# accBoard.net
KiCad netlist of a schematic drawn in EAGLE
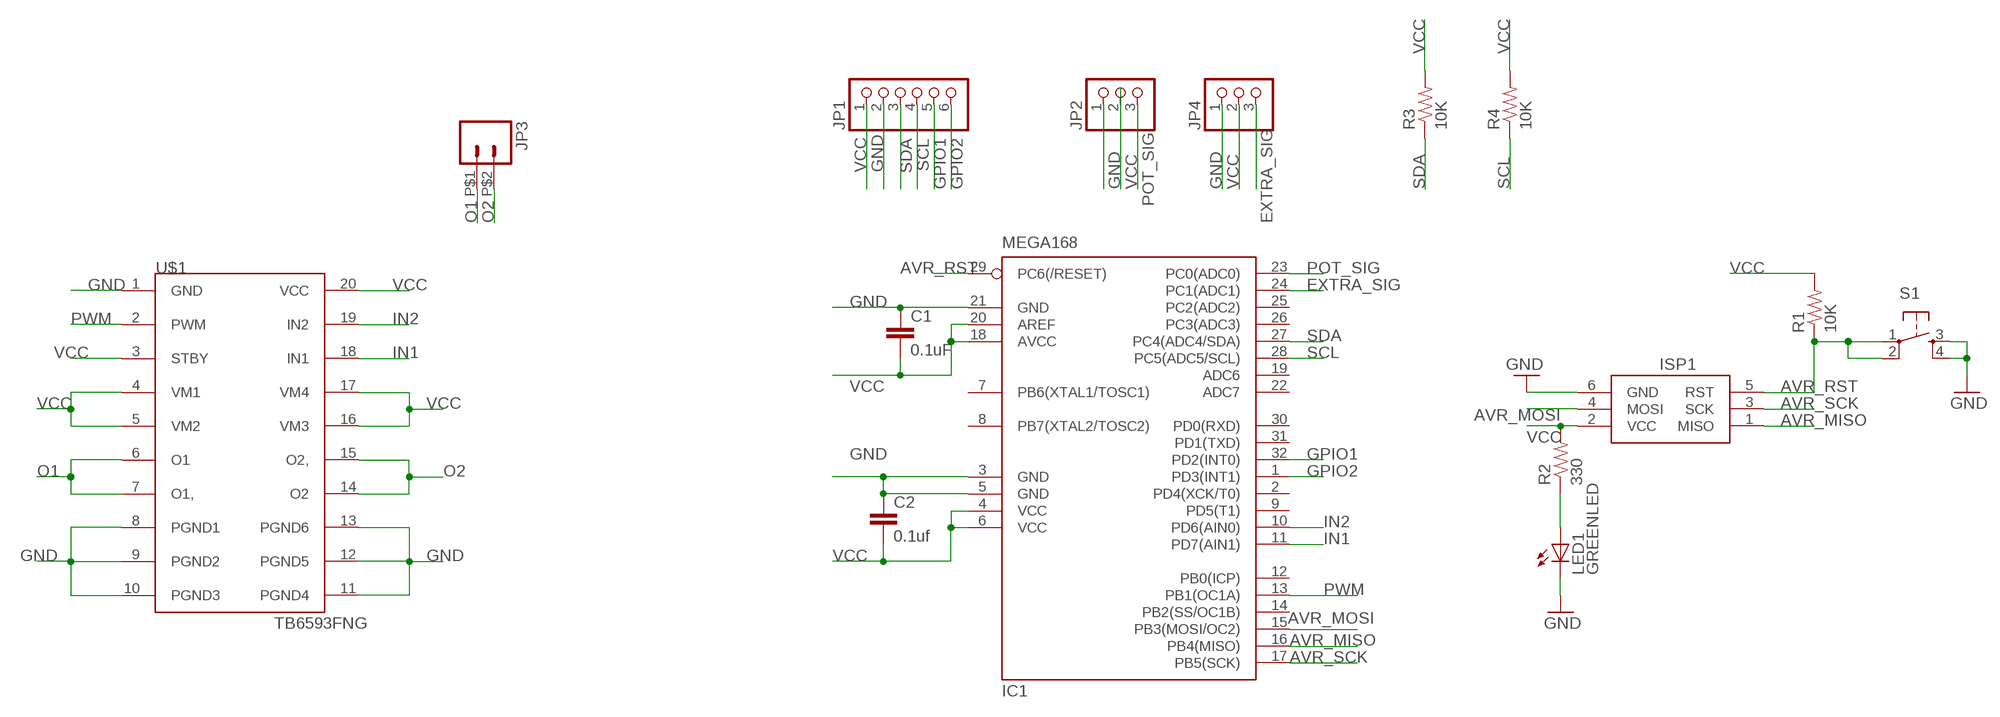
[diagram p0: schematic, sheet 1]

(export (version "E")
  (design (tool "Eeschema 10.0.6"))
  (components
    (comp (ref "C1")
      (value "0.1uF")
      (footprint "eagle-import:0603-CAP")
      (libsource (lib "eagle-import") (part "CAP0603-CAP"))
    )
    (comp (ref "C2")
      (value "0.1uf")
      (footprint "eagle-import:0603-CAP")
      (libsource (lib "eagle-import") (part "CAP0603-CAP"))
    )
    (comp (ref "IC1")
      (value "MEGA168")
      (footprint "eagle-import:TQFP32-08")
      (fields (field (name "MPN") "ATMEGA8-16AU"))
      (libsource (lib "eagle-import") (part "MEGA8-AI"))
    )
    (comp (ref "ISP1")
      (value "AVRISP-6")
      (footprint "eagle-import:AVRISP")
      (libsource (lib "eagle-import") (part "AVRISP-6"))
    )
    (comp (ref "JP1")
      (value "PINHD-1X6")
      (footprint "eagle-import:1X06")
      (libsource (lib "eagle-import") (part "PINHD-1X6"))
    )
    (comp (ref "JP2")
      (value "PINHD-1X3")
      (footprint "eagle-import:1X03")
      (libsource (lib "eagle-import") (part "PINHD-1X3"))
    )
    (comp (ref "JP3")
      (value "M02PTH2")
      (footprint "eagle-import:1X02_BIG")
      (libsource (lib "eagle-import") (part "M02PTH2"))
    )
    (comp (ref "JP4")
      (value "PINHD-1X3")
      (footprint "eagle-import:1X03")
      (libsource (lib "eagle-import") (part "PINHD-1X3"))
    )
    (comp (ref "LED1")
      (value "GREENLED")
      (footprint "eagle-import:LED-0603")
      (libsource (lib "eagle-import") (part "LED0603"))
    )
    (comp (ref "R1")
      (value "10K")
      (footprint "eagle-import:0603-RES")
      (libsource (lib "eagle-import") (part "RESISTOR0603-RES"))
    )
    (comp (ref "R2")
      (value "330")
      (footprint "eagle-import:0603-RES")
      (libsource (lib "eagle-import") (part "RESISTOR0603-RES"))
    )
    (comp (ref "R3")
      (value "10K")
      (footprint "eagle-import:0603-RES")
      (libsource (lib "eagle-import") (part "RESISTOR0603-RES"))
    )
    (comp (ref "R4")
      (value "10K")
      (footprint "eagle-import:0603-RES")
      (libsource (lib "eagle-import") (part "RESISTOR0603-RES"))
    )
    (comp (ref "S1")
      (value "TAC_SWITCHSMD")
      (footprint "eagle-import:TACTILE_SWITCH_SMD")
      (libsource (lib "eagle-import") (part "TAC_SWITCHSMD"))
    )
    (comp (ref "U$1")
      (value "TB6593FNG")
      (footprint "eagle-import:SSOP20")
      (libsource (lib "eagle-import") (part "TB6593FNG"))
    )
  )
  (nets
    (net (code "1") (name "/AVR_MISO") (class "Default")
      (node (ref "IC1") (pin "16") (pinfunction "PB4(MISO)_16") (pintype "bidirectional"))
      (node (ref "ISP1") (pin "1") (pinfunction "MISO_1") (pintype "input"))
    )
    (net (code "2") (name "/AVR_MOSI") (class "Default")
      (node (ref "IC1") (pin "15") (pinfunction "PB3(MOSI/OC2)_15") (pintype "bidirectional"))
      (node (ref "ISP1") (pin "4") (pinfunction "MOSI_4") (pintype "output"))
    )
    (net (code "3") (name "/AVR_RST") (class "Default")
      (node (ref "IC1") (pin "29") (pinfunction "PC6(/RESET)_29") (pintype "bidirectional"))
      (node (ref "ISP1") (pin "5") (pinfunction "RST_5") (pintype "output"))
      (node (ref "R1") (pin "1") (pinfunction "1_1") (pintype "passive"))
      (node (ref "S1") (pin "1") (pinfunction "1_1") (pintype "passive"))
      (node (ref "S1") (pin "2") (pinfunction "2_2") (pintype "passive"))
    )
    (net (code "4") (name "/AVR_SCK") (class "Default")
      (node (ref "IC1") (pin "17") (pinfunction "PB5(SCK)_17") (pintype "bidirectional"))
      (node (ref "ISP1") (pin "3") (pinfunction "SCK_3") (pintype "output"))
    )
    (net (code "5") (name "/EXTRA_SIG") (class "Default")
      (node (ref "IC1") (pin "24") (pinfunction "PC1(ADC1)_24") (pintype "bidirectional"))
      (node (ref "JP4") (pin "3") (pinfunction "3_3") (pintype "passive"))
    )
    (net (code "6") (name "/GPIO1") (class "Default")
      (node (ref "IC1") (pin "32") (pinfunction "PD2(INT0)_32") (pintype "bidirectional"))
      (node (ref "JP1") (pin "5") (pinfunction "5_5") (pintype "passive"))
    )
    (net (code "7") (name "/GPIO2") (class "Default")
      (node (ref "IC1") (pin "1") (pinfunction "PD3(INT1)_1") (pintype "bidirectional"))
      (node (ref "JP1") (pin "6") (pinfunction "6_6") (pintype "passive"))
    )
    (net (code "8") (name "/IN1") (class "Default")
      (node (ref "IC1") (pin "11") (pinfunction "PD7(AIN1)_11") (pintype "bidirectional"))
      (node (ref "U$1") (pin "18") (pinfunction "IN1_18") (pintype "bidirectional"))
    )
    (net (code "9") (name "/IN2") (class "Default")
      (node (ref "IC1") (pin "10") (pinfunction "PD6(AIN0)_10") (pintype "bidirectional"))
      (node (ref "U$1") (pin "19") (pinfunction "IN2_19") (pintype "bidirectional"))
    )
    (net (code "10") (name "/O1") (class "Default")
      (node (ref "JP3") (pin "P$1") (pinfunction "1_P$1") (pintype "passive"))
      (node (ref "U$1") (pin "6") (pinfunction "O1_6") (pintype "bidirectional"))
      (node (ref "U$1") (pin "7") (pinfunction "O1,_7") (pintype "bidirectional"))
    )
    (net (code "11") (name "/O2") (class "Default")
      (node (ref "JP3") (pin "P$2") (pinfunction "2_P$2") (pintype "passive"))
      (node (ref "U$1") (pin "14") (pinfunction "O2_14") (pintype "bidirectional"))
      (node (ref "U$1") (pin "15") (pinfunction "O2,_15") (pintype "bidirectional"))
    )
    (net (code "12") (name "/POT_SIG") (class "Default")
      (node (ref "IC1") (pin "23") (pinfunction "PC0(ADC0)_23") (pintype "bidirectional"))
      (node (ref "JP2") (pin "3") (pinfunction "3_3") (pintype "passive"))
    )
    (net (code "13") (name "/PWM") (class "Default")
      (node (ref "IC1") (pin "13") (pinfunction "PB1(OC1A)_13") (pintype "bidirectional"))
      (node (ref "U$1") (pin "2") (pinfunction "PWM_2") (pintype "bidirectional"))
    )
    (net (code "14") (name "/SCL") (class "Default")
      (node (ref "IC1") (pin "28") (pinfunction "PC5(ADC5/SCL)_28") (pintype "bidirectional"))
      (node (ref "JP1") (pin "4") (pinfunction "4_4") (pintype "passive"))
      (node (ref "R4") (pin "1") (pinfunction "1_1") (pintype "passive"))
    )
    (net (code "15") (name "/SDA") (class "Default")
      (node (ref "IC1") (pin "27") (pinfunction "PC4(ADC4/SDA)_27") (pintype "bidirectional"))
      (node (ref "JP1") (pin "3") (pinfunction "3_3") (pintype "passive"))
      (node (ref "R3") (pin "1") (pinfunction "1_1") (pintype "passive"))
    )
    (net (code "16") (name "/VCC") (class "Default")
      (node (ref "C1") (pin "2") (pinfunction "2_2") (pintype "passive"))
      (node (ref "C2") (pin "2") (pinfunction "2_2") (pintype "passive"))
      (node (ref "IC1") (pin "18") (pinfunction "AVCC_18") (pintype "power_in"))
      (node (ref "IC1") (pin "20") (pinfunction "AREF_20") (pintype "passive"))
      (node (ref "IC1") (pin "4") (pinfunction "VCC_4") (pintype "power_in"))
      (node (ref "IC1") (pin "6") (pinfunction "VCC_6") (pintype "power_in"))
      (node (ref "ISP1") (pin "2") (pinfunction "VCC_2") (pintype "power_in"))
      (node (ref "JP1") (pin "1") (pinfunction "1_1") (pintype "passive"))
      (node (ref "JP2") (pin "2") (pinfunction "2_2") (pintype "passive"))
      (node (ref "JP4") (pin "2") (pinfunction "2_2") (pintype "passive"))
      (node (ref "R1") (pin "2") (pinfunction "2_2") (pintype "passive"))
      (node (ref "R2") (pin "2") (pinfunction "2_2") (pintype "passive"))
      (node (ref "R3") (pin "2") (pinfunction "2_2") (pintype "passive"))
      (node (ref "R4") (pin "2") (pinfunction "2_2") (pintype "passive"))
      (node (ref "U$1") (pin "16") (pinfunction "VM3_16") (pintype "bidirectional"))
      (node (ref "U$1") (pin "17") (pinfunction "VM4_17") (pintype "bidirectional"))
      (node (ref "U$1") (pin "20") (pinfunction "VCC_20") (pintype "bidirectional"))
      (node (ref "U$1") (pin "3") (pinfunction "STBY_3") (pintype "bidirectional"))
      (node (ref "U$1") (pin "4") (pinfunction "VM1_4") (pintype "bidirectional"))
      (node (ref "U$1") (pin "5") (pinfunction "VM2_5") (pintype "bidirectional"))
    )
    (net (code "17") (name "GND") (class "Default")
      (node (ref "C1") (pin "1") (pinfunction "1_1") (pintype "passive"))
      (node (ref "C2") (pin "1") (pinfunction "1_1") (pintype "passive"))
      (node (ref "IC1") (pin "21") (pinfunction "GND_21") (pintype "power_in"))
      (node (ref "IC1") (pin "3") (pinfunction "GND_3") (pintype "power_in"))
      (node (ref "IC1") (pin "5") (pinfunction "GND_5") (pintype "power_in"))
      (node (ref "ISP1") (pin "6") (pinfunction "GND_6") (pintype "power_in"))
      (node (ref "JP1") (pin "2") (pinfunction "2_2") (pintype "passive"))
      (node (ref "JP2") (pin "1") (pinfunction "1_1") (pintype "passive"))
      (node (ref "JP4") (pin "1") (pinfunction "1_1") (pintype "passive"))
      (node (ref "LED1") (pin "C") (pinfunction "C_C") (pintype "passive"))
      (node (ref "S1") (pin "3") (pinfunction "3_3") (pintype "passive"))
      (node (ref "S1") (pin "4") (pinfunction "4_4") (pintype "passive"))
      (node (ref "U$1") (pin "1") (pinfunction "GND_1") (pintype "bidirectional"))
      (node (ref "U$1") (pin "10") (pinfunction "PGND3_10") (pintype "bidirectional"))
      (node (ref "U$1") (pin "11") (pinfunction "PGND4_11") (pintype "bidirectional"))
      (node (ref "U$1") (pin "12") (pinfunction "PGND5_12") (pintype "bidirectional"))
      (node (ref "U$1") (pin "13") (pinfunction "PGND6_13") (pintype "bidirectional"))
      (node (ref "U$1") (pin "8") (pinfunction "PGND1_8") (pintype "bidirectional"))
      (node (ref "U$1") (pin "9") (pinfunction "PGND2_9") (pintype "bidirectional"))
    )
    (net (code "18") (name "Net-(LED1-PadA)") (class "Default")
      (node (ref "LED1") (pin "A") (pinfunction "A_A") (pintype "passive"))
      (node (ref "R2") (pin "1") (pinfunction "1_1") (pintype "passive"))
    )
    (net (code "19") (name "unconnected-(IC1-ADC6-Pad19)") (class "Default")
      (node (ref "IC1") (pin "19") (pinfunction "ADC6_19") (pintype "bidirectional"))
    )
    (net (code "20") (name "unconnected-(IC1-ADC7-Pad22)") (class "Default")
      (node (ref "IC1") (pin "22") (pinfunction "ADC7_22") (pintype "bidirectional"))
    )
    (net (code "21") (name "unconnected-(IC1-PB0(ICP)-Pad12)") (class "Default")
      (node (ref "IC1") (pin "12") (pinfunction "PB0(ICP)_12") (pintype "bidirectional"))
    )
    (net (code "22") (name "unconnected-(IC1-PB2(SS{slash}OC1B)-Pad14)") (class "Default")
      (node (ref "IC1") (pin "14") (pinfunction "PB2(SS/OC1B)_14") (pintype "bidirectional"))
    )
    (net (code "23") (name "unconnected-(IC1-PB6(XTAL1{slash}TOSC1)-Pad7)") (class "Default")
      (node (ref "IC1") (pin "7") (pinfunction "PB6(XTAL1/TOSC1)_7") (pintype "bidirectional"))
    )
    (net (code "24") (name "unconnected-(IC1-PB7(XTAL2{slash}TOSC2)-Pad8)") (class "Default")
      (node (ref "IC1") (pin "8") (pinfunction "PB7(XTAL2/TOSC2)_8") (pintype "bidirectional"))
    )
    (net (code "25") (name "unconnected-(IC1-PC2(ADC2)-Pad25)") (class "Default")
      (node (ref "IC1") (pin "25") (pinfunction "PC2(ADC2)_25") (pintype "bidirectional"))
    )
    (net (code "26") (name "unconnected-(IC1-PC3(ADC3)-Pad26)") (class "Default")
      (node (ref "IC1") (pin "26") (pinfunction "PC3(ADC3)_26") (pintype "bidirectional"))
    )
    (net (code "27") (name "unconnected-(IC1-PD0(RXD)-Pad30)") (class "Default")
      (node (ref "IC1") (pin "30") (pinfunction "PD0(RXD)_30") (pintype "bidirectional"))
    )
    (net (code "28") (name "unconnected-(IC1-PD1(TXD)-Pad31)") (class "Default")
      (node (ref "IC1") (pin "31") (pinfunction "PD1(TXD)_31") (pintype "bidirectional"))
    )
    (net (code "29") (name "unconnected-(IC1-PD4(XCK{slash}T0)-Pad2)") (class "Default")
      (node (ref "IC1") (pin "2") (pinfunction "PD4(XCK/T0)_2") (pintype "bidirectional"))
    )
    (net (code "30") (name "unconnected-(IC1-PD5(T1)-Pad9)") (class "Default")
      (node (ref "IC1") (pin "9") (pinfunction "PD5(T1)_9") (pintype "bidirectional"))
    )
  )
)
